# LED_Button.net
KiCad netlist of a schematic drawn in Altium Designer
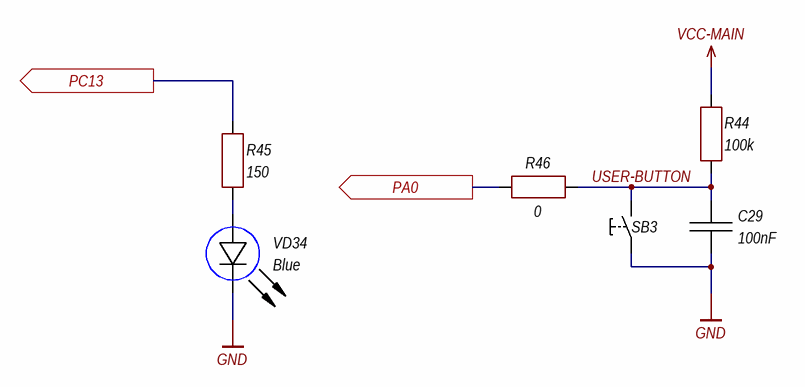
[diagram p0: LED&Button.SchDoc]

(export (version "E")
  (design (tool "Eeschema 10.0.6"))
  (components
    (comp (ref "C29") (value "100nF") (footprint "CH0402C") (libsource (lib "Discrete") (part "Capacitor")))
    (comp (ref "R44") (value "100k") (footprint "CH0402R") (libsource (lib "Discrete") (part "Resistor")))
    (comp (ref "R45") (value "150") (footprint "CH0402R") (libsource (lib "Discrete") (part "Resistor")))
    (comp (ref "R46") (value "0") (footprint "CH0402R") (libsource (lib "") (part "Resistor_1")))
    (comp (ref "SB3")
      (value "\"Кнопка\"")
      (footprint "BUT: YTS-A017")
      (description "Button, no latching")
      (libsource (lib "Connectors") (part "1-Button"))
    )
    (comp (ref "VD34") (value "Blue") (footprint "CH0402LG") (libsource (lib "Discrete") (part "LED")))
  )
  (nets
    (net (code "1") (name "/PA0") (class "Default")
      (node (ref "R46") (pin "1") (pinfunction "1_1") (pintype "passive"))
    )
    (net (code "2") (name "/PC13") (class "Default")
      (node (ref "R45") (pin "2") (pinfunction "2_2") (pintype "passive"))
    )
    (net (code "3") (name "/USER-BUTTON") (class "Default")
      (node (ref "C29") (pin "2") (pinfunction "2_2") (pintype "passive"))
      (node (ref "R44") (pin "1") (pinfunction "1_1") (pintype "passive"))
      (node (ref "R46") (pin "2") (pinfunction "2_2") (pintype "passive"))
      (node (ref "SB3") (pin "2") (pinfunction "2_2") (pintype "passive"))
    )
    (net (code "4") (name "GND") (class "Default")
      (node (ref "C29") (pin "1") (pinfunction "1_1") (pintype "passive"))
      (node (ref "SB3") (pin "1") (pinfunction "1_1") (pintype "passive"))
      (node (ref "VD34") (pin "2") (pinfunction "C_2") (pintype "passive"))
    )
    (net (code "5") (name "Net-(VD34-A)") (class "Default")
      (node (ref "R45") (pin "1") (pinfunction "1_1") (pintype "passive"))
      (node (ref "VD34") (pin "1") (pinfunction "A_1") (pintype "passive"))
    )
    (net (code "6") (name "VCC-MAIN") (class "Default")
      (node (ref "R44") (pin "2") (pinfunction "2_2") (pintype "passive"))
    )
  )
)
